# UnRegPower.net
KiCad netlist of a schematic drawn in Altium Designer
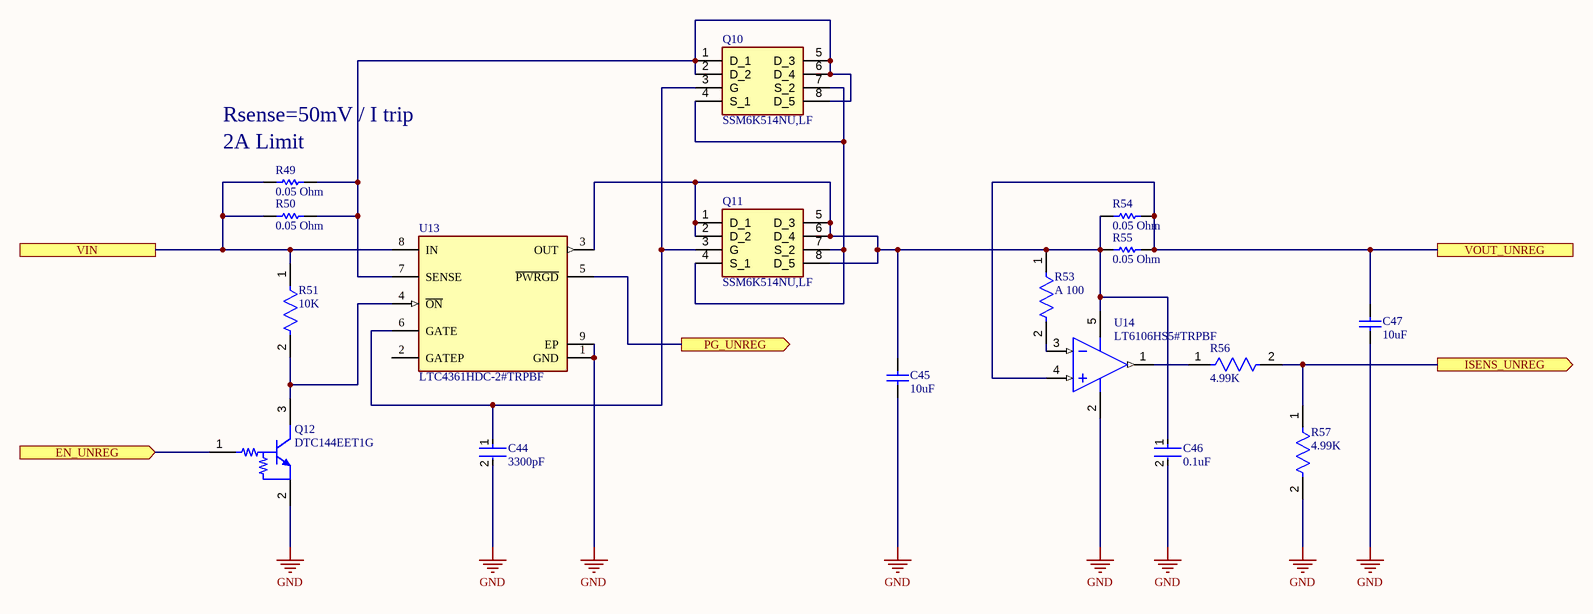
[diagram p0: UnRegPower.SchDoc]

(export (version "E")
  (design (tool "Eeschema 10.0.6"))
  (components
    (comp (ref "C44")
      (value "3300pF")
      (footprint "FP-C0603C-CF-MFG")
      (description "CAP CER 3300PF 50V 5% X7R 0603")
      (fields
        (field (name "MANUFACTURER PART NUMBER") "C0603C332J5RACTU")
        (field (name "MANUFACTURER") "KEMET")
      )
      (libsource (lib "Altium Content Vault") (part "b4654b650e69147ec39a6b967a45e02"))
    )
    (comp (ref "C45")
      (value "10uF")
      (footprint "CAPC2013X140X45NL15T25")
      (fields (field (name "PART NUMBER") "GRM21BR71A106KE51L") (field (name "MANUFACTURER") "Murata"))
      (libsource (lib "Altium Content Vault") (part "CAP"))
    )
    (comp (ref "C46")
      (value "0.1uF")
      (footprint "FP-C0603C-CF-MFG")
      (description "CAP CER 0.1UF 50V X7R 0603")
      (fields (field (name "TOLERANCE") "0.1") (field (name "MANUFACTURER") "KEMET"))
      (libsource (lib "Altium Content Vault") (part "b4654b650e69147ec39a6b967a45e02"))
    )
    (comp (ref "C47")
      (value "10uF")
      (footprint "CAPC2013X140X45NL15T25")
      (fields (field (name "PART NUMBER") "GRM21BR71A106KE51L") (field (name "MANUFACTURER") "Murata"))
      (libsource (lib "Altium Content Vault") (part "CAP"))
    )
    (comp (ref "Q10")
      (value "SSM6K514NU,LF")
      (footprint "SamacSys:UDFN6B")
      (description "MOSFET (N-Channel)")
      (fields (field (name "MOUSER PART NUMBER") "757-SSM6K514NULF"))
      (libsource (lib "*") (part "SSM6K514NU,LF"))
    )
    (comp (ref "Q11")
      (value "SSM6K514NU,LF")
      (footprint "SamacSys:UDFN6B")
      (description "MOSFET (N-Channel)")
      (fields (field (name "MOUSER PART NUMBER") "757-SSM6K514NULF"))
      (libsource (lib "*") (part "SSM6K514NU,LF"))
    )
    (comp (ref "Q12")
      (value "DTC144EET1G")
      (footprint "ONSC-SC-75-3-463-01_V")
      (fields (field (name "MANUFACTURER") "On Semiconductor"))
      (libsource (lib "Altium Content Vault") (part "ONSC-BRT-NPN-B1E2C3-3"))
    )
    (comp (ref "R49")
      (value "0.05 Ohm")
      (footprint "RESC1608X55X30NL15T15")
      (fields (field (name "MANUFACTURER") "Panasonic") (field (name "PART NUMBER") "ERJ-L03KF50MV"))
      (libsource (lib "Altium Content Vault") (part "RES"))
    )
    (comp (ref "R50")
      (value "0.05 Ohm")
      (footprint "RESC1608X55X30NL15T15")
      (fields (field (name "MANUFACTURER") "Panasonic") (field (name "PART NUMBER") "ERJ-L03KF50MV"))
      (libsource (lib "Altium Content Vault") (part "RES"))
    )
    (comp (ref "R51")
      (value "10K")
      (footprint "FP-RK73B1J-MFG")
      (description "RES 10K OHM 5% 1/10W 0603")
      (fields (field (name "TOLERANCE") "5%"))
      (libsource (lib "Altium Content Vault") (part "1029c3af85768c4190bb7ad29bc67b5"))
    )
    (comp (ref "R53")
      (value "A 100")
      (footprint "FP-ERA3A-IPC_B")
      (description "RES SMD 100 OHM 0.1% 1/10W 0603")
      (fields (field (name "TOLERANCE") "0.1%"))
      (libsource (lib "Altium Content Vault") (part "1029c3af85768c4190bb7ad29bc67b5"))
    )
    (comp (ref "R54")
      (value "0.05 Ohm")
      (footprint "RESC1608X55X30NL15T15")
      (fields (field (name "MANUFACTURER") "Panasonic") (field (name "PART NUMBER") "ERJ-L03KF50MV"))
      (libsource (lib "Altium Content Vault") (part "RES"))
    )
    (comp (ref "R55")
      (value "0.05 Ohm")
      (footprint "RESC1608X55X30NL15T15")
      (fields (field (name "MANUFACTURER") "Panasonic") (field (name "PART NUMBER") "ERJ-L03KF50MV"))
      (libsource (lib "Altium Content Vault") (part "RES"))
    )
    (comp (ref "R56")
      (value "4.99K")
      (footprint "FP-ERA3A-IPC_C")
      (description "RES SMD 4.99KOHM 0.1% 1/10W 0603")
      (fields (field (name "TOLERANCE") "0.1%"))
      (libsource (lib "Altium Content Vault") (part "1029c3af85768c4190bb7ad29bc67b5"))
    )
    (comp (ref "R57")
      (value "4.99K")
      (footprint "FP-ERA3A-IPC_C")
      (description "RES SMD 4.99KOHM 0.1% 1/10W 0603")
      (fields (field (name "TOLERANCE") "0.1%"))
      (libsource (lib "Altium Content Vault") (part "1029c3af85768c4190bb7ad29bc67b5"))
    )
    (comp (ref "U13")
      (value "LTC4361HDC-2#TRPBF")
      (footprint "FP-DC8-8-05-08-1719-IPC_C")
      (description "IC OVP/OCP PROTECTION CTLR 8DFN")
      (libsource (lib "Altium Content Vault") (part "fbb45dfe5e09bf71f23ab0fd2a2f1dd"))
    )
    (comp (ref "U14")
      (value "LT6106HS5#TRPBF")
      (footprint "LT-S5-5-TSOT-23_M")
      (fields
        (field (name "MANUFACTURER") "Linear Technology")
        (field (name "LINEAR TECHNOLOGY PART NUMBER") "LT6106")
      )
      (libsource (lib "Altium Content Vault") (part "LT-LT6106-LTC6101HV-5"))
    )
  )
  (nets
    (net (code "1") (name "/EN_UNREG") (class "Default")
      (node (ref "Q12") (pin "1") (pinfunction "B_1") (pintype "passive"))
    )
    (net (code "2") (name "/ISENS_UNREG") (class "Default")
      (node (ref "R56") (pin "2") (pinfunction "2_2") (pintype "passive"))
      (node (ref "R57") (pin "1") (pinfunction "1_1") (pintype "passive"))
    )
    (net (code "3") (name "/PG_UNREG") (class "Default")
      (node (ref "U13") (pin "5") (pinfunction "~{PWRGD}_5") (pintype "open_collector"))
    )
    (net (code "4") (name "/VIN") (class "Default")
      (node (ref "R49") (pin "1") (pinfunction "1_1") (pintype "passive"))
      (node (ref "R50") (pin "1") (pinfunction "1_1") (pintype "passive"))
      (node (ref "R51") (pin "1") (pinfunction "1_1") (pintype "passive"))
      (node (ref "U13") (pin "8") (pinfunction "IN_8") (pintype "power_in"))
    )
    (net (code "5") (name "/VOUT_UNREG") (class "Default")
      (node (ref "C47") (pin "2") (pinfunction "2_2") (pintype "passive"))
      (node (ref "R54") (pin "2") (pinfunction "2_2") (pintype "passive"))
      (node (ref "R55") (pin "2") (pinfunction "2_2") (pintype "passive"))
      (node (ref "U14") (pin "4") (pinfunction "+IN_4") (pintype "input"))
    )
    (net (code "6") (name "GND") (class "Default")
      (node (ref "C44") (pin "2") (pinfunction "2_2") (pintype "passive"))
      (node (ref "C45") (pin "1") (pinfunction "1_1") (pintype "passive"))
      (node (ref "C46") (pin "2") (pinfunction "2_2") (pintype "passive"))
      (node (ref "C47") (pin "1") (pinfunction "1_1") (pintype "passive"))
      (node (ref "Q12") (pin "2") (pinfunction "E_2") (pintype "passive"))
      (node (ref "R57") (pin "2") (pinfunction "2_2") (pintype "passive"))
      (node (ref "U13") (pin "1") (pinfunction "GND_1") (pintype "power_in"))
      (node (ref "U13") (pin "9") (pinfunction "EP_9") (pintype "power_in"))
      (node (ref "U14") (pin "2") (pinfunction "V-_2") (pintype "power_in"))
    )
    (net (code "7") (name "Net-(Q10-D_1)") (class "Default")
      (node (ref "Q10") (pin "1") (pinfunction "D_1_1") (pintype "passive"))
      (node (ref "Q10") (pin "2") (pinfunction "D_2_2") (pintype "passive"))
      (node (ref "Q10") (pin "5") (pinfunction "D_3_5") (pintype "passive"))
      (node (ref "Q10") (pin "6") (pinfunction "D_4_6") (pintype "passive"))
      (node (ref "Q10") (pin "8") (pinfunction "D_5_8") (pintype "passive"))
      (node (ref "R49") (pin "2") (pinfunction "2_2") (pintype "passive"))
      (node (ref "R50") (pin "2") (pinfunction "2_2") (pintype "passive"))
      (node (ref "U13") (pin "7") (pinfunction "SENSE_7") (pintype "passive"))
    )
    (net (code "8") (name "Net-(Q10-G)") (class "Default")
      (node (ref "C44") (pin "1") (pinfunction "1_1") (pintype "passive"))
      (node (ref "Q10") (pin "3") (pinfunction "G_3") (pintype "passive"))
      (node (ref "Q11") (pin "3") (pinfunction "G_3") (pintype "passive"))
      (node (ref "U13") (pin "6") (pinfunction "GATE_6") (pintype "passive"))
    )
    (net (code "9") (name "Net-(Q10-S_1)") (class "Default")
      (node (ref "Q10") (pin "4") (pinfunction "S_1_4") (pintype "passive"))
      (node (ref "Q10") (pin "7") (pinfunction "S_2_7") (pintype "passive"))
      (node (ref "Q11") (pin "4") (pinfunction "S_1_4") (pintype "passive"))
      (node (ref "Q11") (pin "7") (pinfunction "S_2_7") (pintype "passive"))
    )
    (net (code "10") (name "Net-(Q11-D_1)") (class "Default")
      (node (ref "C45") (pin "2") (pinfunction "2_2") (pintype "passive"))
      (node (ref "C46") (pin "1") (pinfunction "1_1") (pintype "passive"))
      (node (ref "Q11") (pin "1") (pinfunction "D_1_1") (pintype "passive"))
      (node (ref "Q11") (pin "2") (pinfunction "D_2_2") (pintype "passive"))
      (node (ref "Q11") (pin "5") (pinfunction "D_3_5") (pintype "passive"))
      (node (ref "Q11") (pin "6") (pinfunction "D_4_6") (pintype "passive"))
      (node (ref "Q11") (pin "8") (pinfunction "D_5_8") (pintype "passive"))
      (node (ref "R53") (pin "1") (pinfunction "1_1") (pintype "passive"))
      (node (ref "R54") (pin "1") (pinfunction "1_1") (pintype "passive"))
      (node (ref "R55") (pin "1") (pinfunction "1_1") (pintype "passive"))
      (node (ref "U13") (pin "3") (pinfunction "OUT_3") (pintype "output"))
      (node (ref "U14") (pin "5") (pinfunction "V+_5") (pintype "power_in"))
    )
    (net (code "11") (name "Net-(Q12-C)") (class "Default")
      (node (ref "Q12") (pin "3") (pinfunction "C_3") (pintype "passive"))
      (node (ref "R51") (pin "2") (pinfunction "2_2") (pintype "passive"))
      (node (ref "U13") (pin "4") (pinfunction "~{ON}_4") (pintype "input"))
    )
    (net (code "12") (name "Net-(U14--IN)") (class "Default")
      (node (ref "R53") (pin "2") (pinfunction "2_2") (pintype "passive"))
      (node (ref "U14") (pin "3") (pinfunction "-IN_3") (pintype "input"))
    )
    (net (code "13") (name "Net-(U14-OUT)") (class "Default")
      (node (ref "R56") (pin "1") (pinfunction "1_1") (pintype "passive"))
      (node (ref "U14") (pin "1") (pinfunction "OUT_1") (pintype "output"))
    )
    (net (code "14") (name "unconnected-(U13-GATEP-Pad2)") (class "Default")
      (node (ref "U13") (pin "2") (pinfunction "GATEP_2") (pintype "passive"))
    )
  )
)
